# Artix7_Power_Grounds.net
KiCad netlist of a schematic drawn in Altium Designer
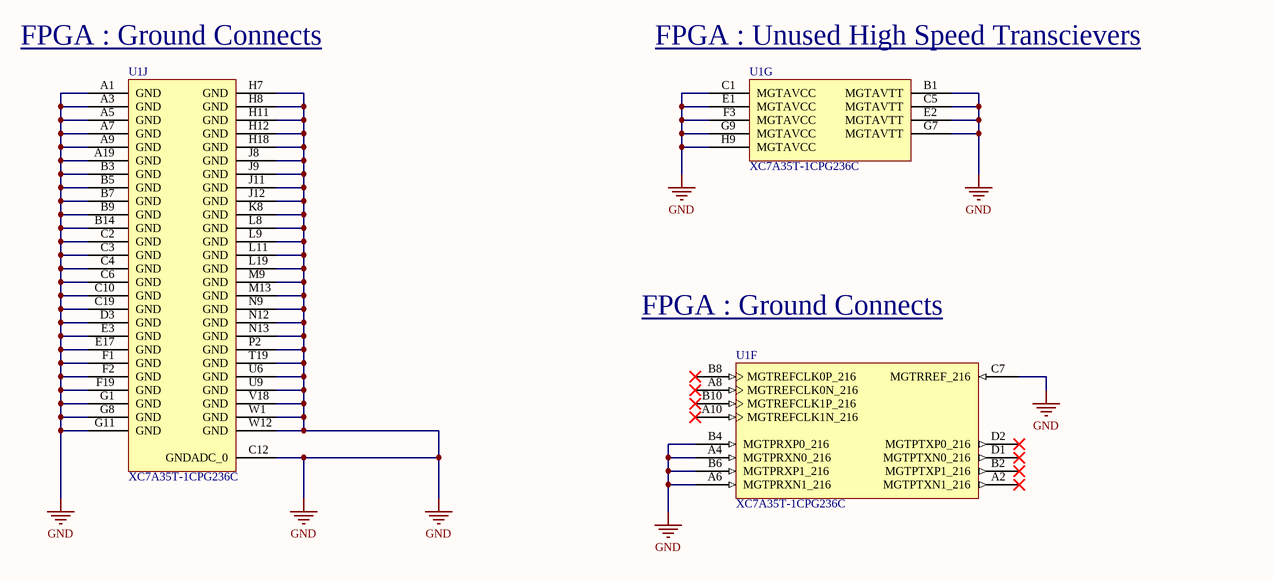
[diagram p0: Artix7_Power_Grounds.SchDoc]

(export (version "E")
  (design (tool "Eeschema 10.0.6"))
  (components
    (comp (ref "U1")
      (value "XC7A35T-1CPG236C")
      (footprint "CPG236")
      (description "Artix-7 FPGA, 106 User I/Os, 2 GTP, 238-Ball BGA, Speed Grade 1, Commercial Grade, Pb-Free")
      (fields (field (name "MANUFACTURER") "Xilinx"))
      (libsource (lib "Altium Content Vault") (part "XLNX-XC7A35T-CPG236"))
    )
  )
  (nets
    (net (code "1") (name "GND") (class "Default")
      (node (ref "U1") (pin "A1") (pinfunction "GND_A1") (pintype "power_in"))
      (node (ref "U1") (pin "A19") (pinfunction "GND_A19") (pintype "power_in"))
      (node (ref "U1") (pin "A3") (pinfunction "GND_A3") (pintype "power_in"))
      (node (ref "U1") (pin "A4") (pinfunction "MGTPRXN0_216_A4") (pintype "input"))
      (node (ref "U1") (pin "A5") (pinfunction "GND_A5") (pintype "power_in"))
      (node (ref "U1") (pin "A6") (pinfunction "MGTPRXN1_216_A6") (pintype "input"))
      (node (ref "U1") (pin "A7") (pinfunction "GND_A7") (pintype "power_in"))
      (node (ref "U1") (pin "A9") (pinfunction "GND_A9") (pintype "power_in"))
      (node (ref "U1") (pin "B1") (pinfunction "MGTAVTT_B1") (pintype "power_in"))
      (node (ref "U1") (pin "B14") (pinfunction "GND_B14") (pintype "power_in"))
      (node (ref "U1") (pin "B3") (pinfunction "GND_B3") (pintype "power_in"))
      (node (ref "U1") (pin "B4") (pinfunction "MGTPRXP0_216_B4") (pintype "input"))
      (node (ref "U1") (pin "B5") (pinfunction "GND_B5") (pintype "power_in"))
      (node (ref "U1") (pin "B6") (pinfunction "MGTPRXP1_216_B6") (pintype "input"))
      (node (ref "U1") (pin "B7") (pinfunction "GND_B7") (pintype "power_in"))
      (node (ref "U1") (pin "B9") (pinfunction "GND_B9") (pintype "power_in"))
      (node (ref "U1") (pin "C1") (pinfunction "MGTAVCC_C1") (pintype "power_in"))
      (node (ref "U1") (pin "C10") (pinfunction "GND_C10") (pintype "power_in"))
      (node (ref "U1") (pin "C12") (pinfunction "GNDADC_0_C12") (pintype "power_in"))
      (node (ref "U1") (pin "C19") (pinfunction "GND_C19") (pintype "power_in"))
      (node (ref "U1") (pin "C2") (pinfunction "GND_C2") (pintype "power_in"))
      (node (ref "U1") (pin "C3") (pinfunction "GND_C3") (pintype "power_in"))
      (node (ref "U1") (pin "C4") (pinfunction "GND_C4") (pintype "power_in"))
      (node (ref "U1") (pin "C5") (pinfunction "MGTAVTT_C5") (pintype "power_in"))
      (node (ref "U1") (pin "C6") (pinfunction "GND_C6") (pintype "power_in"))
      (node (ref "U1") (pin "C7") (pinfunction "MGTRREF_216_C7") (pintype "input"))
      (node (ref "U1") (pin "D3") (pinfunction "GND_D3") (pintype "power_in"))
      (node (ref "U1") (pin "E1") (pinfunction "MGTAVCC_E1") (pintype "power_in"))
      (node (ref "U1") (pin "E17") (pinfunction "GND_E17") (pintype "power_in"))
      (node (ref "U1") (pin "E2") (pinfunction "MGTAVTT_E2") (pintype "power_in"))
      (node (ref "U1") (pin "E3") (pinfunction "GND_E3") (pintype "power_in"))
      (node (ref "U1") (pin "F1") (pinfunction "GND_F1") (pintype "power_in"))
      (node (ref "U1") (pin "F19") (pinfunction "GND_F19") (pintype "power_in"))
      (node (ref "U1") (pin "F2") (pinfunction "GND_F2") (pintype "power_in"))
      (node (ref "U1") (pin "F3") (pinfunction "MGTAVCC_F3") (pintype "power_in"))
      (node (ref "U1") (pin "G1") (pinfunction "GND_G1") (pintype "power_in"))
      (node (ref "U1") (pin "G11") (pinfunction "GND_G11") (pintype "power_in"))
      (node (ref "U1") (pin "G7") (pinfunction "MGTAVTT_G7") (pintype "power_in"))
      (node (ref "U1") (pin "G8") (pinfunction "GND_G8") (pintype "power_in"))
      (node (ref "U1") (pin "G9") (pinfunction "MGTAVCC_G9") (pintype "power_in"))
      (node (ref "U1") (pin "H11") (pinfunction "GND_H11") (pintype "power_in"))
      (node (ref "U1") (pin "H12") (pinfunction "GND_H12") (pintype "power_in"))
      (node (ref "U1") (pin "H18") (pinfunction "GND_H18") (pintype "power_in"))
      (node (ref "U1") (pin "H7") (pinfunction "GND_H7") (pintype "power_in"))
      (node (ref "U1") (pin "H8") (pinfunction "GND_H8") (pintype "power_in"))
      (node (ref "U1") (pin "H9") (pinfunction "MGTAVCC_H9") (pintype "power_in"))
      (node (ref "U1") (pin "J11") (pinfunction "GND_J11") (pintype "power_in"))
      (node (ref "U1") (pin "J12") (pinfunction "GND_J12") (pintype "power_in"))
      (node (ref "U1") (pin "J8") (pinfunction "GND_J8") (pintype "power_in"))
      (node (ref "U1") (pin "J9") (pinfunction "GND_J9") (pintype "power_in"))
      (node (ref "U1") (pin "K8") (pinfunction "GND_K8") (pintype "power_in"))
      (node (ref "U1") (pin "L11") (pinfunction "GND_L11") (pintype "power_in"))
      (node (ref "U1") (pin "L19") (pinfunction "GND_L19") (pintype "power_in"))
      (node (ref "U1") (pin "L8") (pinfunction "GND_L8") (pintype "power_in"))
      (node (ref "U1") (pin "L9") (pinfunction "GND_L9") (pintype "power_in"))
      (node (ref "U1") (pin "M13") (pinfunction "GND_M13") (pintype "power_in"))
      (node (ref "U1") (pin "M9") (pinfunction "GND_M9") (pintype "power_in"))
      (node (ref "U1") (pin "N12") (pinfunction "GND_N12") (pintype "power_in"))
      (node (ref "U1") (pin "N13") (pinfunction "GND_N13") (pintype "power_in"))
      (node (ref "U1") (pin "N9") (pinfunction "GND_N9") (pintype "power_in"))
      (node (ref "U1") (pin "P2") (pinfunction "GND_P2") (pintype "power_in"))
      (node (ref "U1") (pin "T19") (pinfunction "GND_T19") (pintype "power_in"))
      (node (ref "U1") (pin "U6") (pinfunction "GND_U6") (pintype "power_in"))
      (node (ref "U1") (pin "U9") (pinfunction "GND_U9") (pintype "power_in"))
      (node (ref "U1") (pin "V18") (pinfunction "GND_V18") (pintype "power_in"))
      (node (ref "U1") (pin "W1") (pinfunction "GND_W1") (pintype "power_in"))
      (node (ref "U1") (pin "W12") (pinfunction "GND_W12") (pintype "power_in"))
    )
    (net (code "2") (name "unconnected-(U1F-MGTPTXN0_216-PadD1)") (class "Default")
      (node (ref "U1") (pin "D1") (pinfunction "MGTPTXN0_216_D1") (pintype "output+no_connect"))
    )
    (net (code "3") (name "unconnected-(U1F-MGTPTXN1_216-PadA2)") (class "Default")
      (node (ref "U1") (pin "A2") (pinfunction "MGTPTXN1_216_A2") (pintype "output+no_connect"))
    )
    (net (code "4") (name "unconnected-(U1F-MGTPTXP0_216-PadD2)") (class "Default")
      (node (ref "U1") (pin "D2") (pinfunction "MGTPTXP0_216_D2") (pintype "output+no_connect"))
    )
    (net (code "5") (name "unconnected-(U1F-MGTPTXP1_216-PadB2)") (class "Default")
      (node (ref "U1") (pin "B2") (pinfunction "MGTPTXP1_216_B2") (pintype "output+no_connect"))
    )
    (net (code "6") (name "unconnected-(U1F-MGTREFCLK0N_216-PadA8)") (class "Default")
      (node (ref "U1") (pin "A8") (pinfunction "MGTREFCLK0N_216_A8") (pintype "input+no_connect"))
    )
    (net (code "7") (name "unconnected-(U1F-MGTREFCLK0P_216-PadB8)") (class "Default")
      (node (ref "U1") (pin "B8") (pinfunction "MGTREFCLK0P_216_B8") (pintype "input+no_connect"))
    )
    (net (code "8") (name "unconnected-(U1F-MGTREFCLK1N_216-PadA10)") (class "Default")
      (node (ref "U1") (pin "A10") (pinfunction "MGTREFCLK1N_216_A10") (pintype "input+no_connect"))
    )
    (net (code "9") (name "unconnected-(U1F-MGTREFCLK1P_216-PadB10)") (class "Default")
      (node (ref "U1") (pin "B10") (pinfunction "MGTREFCLK1P_216_B10") (pintype "input+no_connect"))
    )
  )
)
